# CY8C4125AZI-S433.net
KiCad netlist of a schematic drawn in Altium Designer
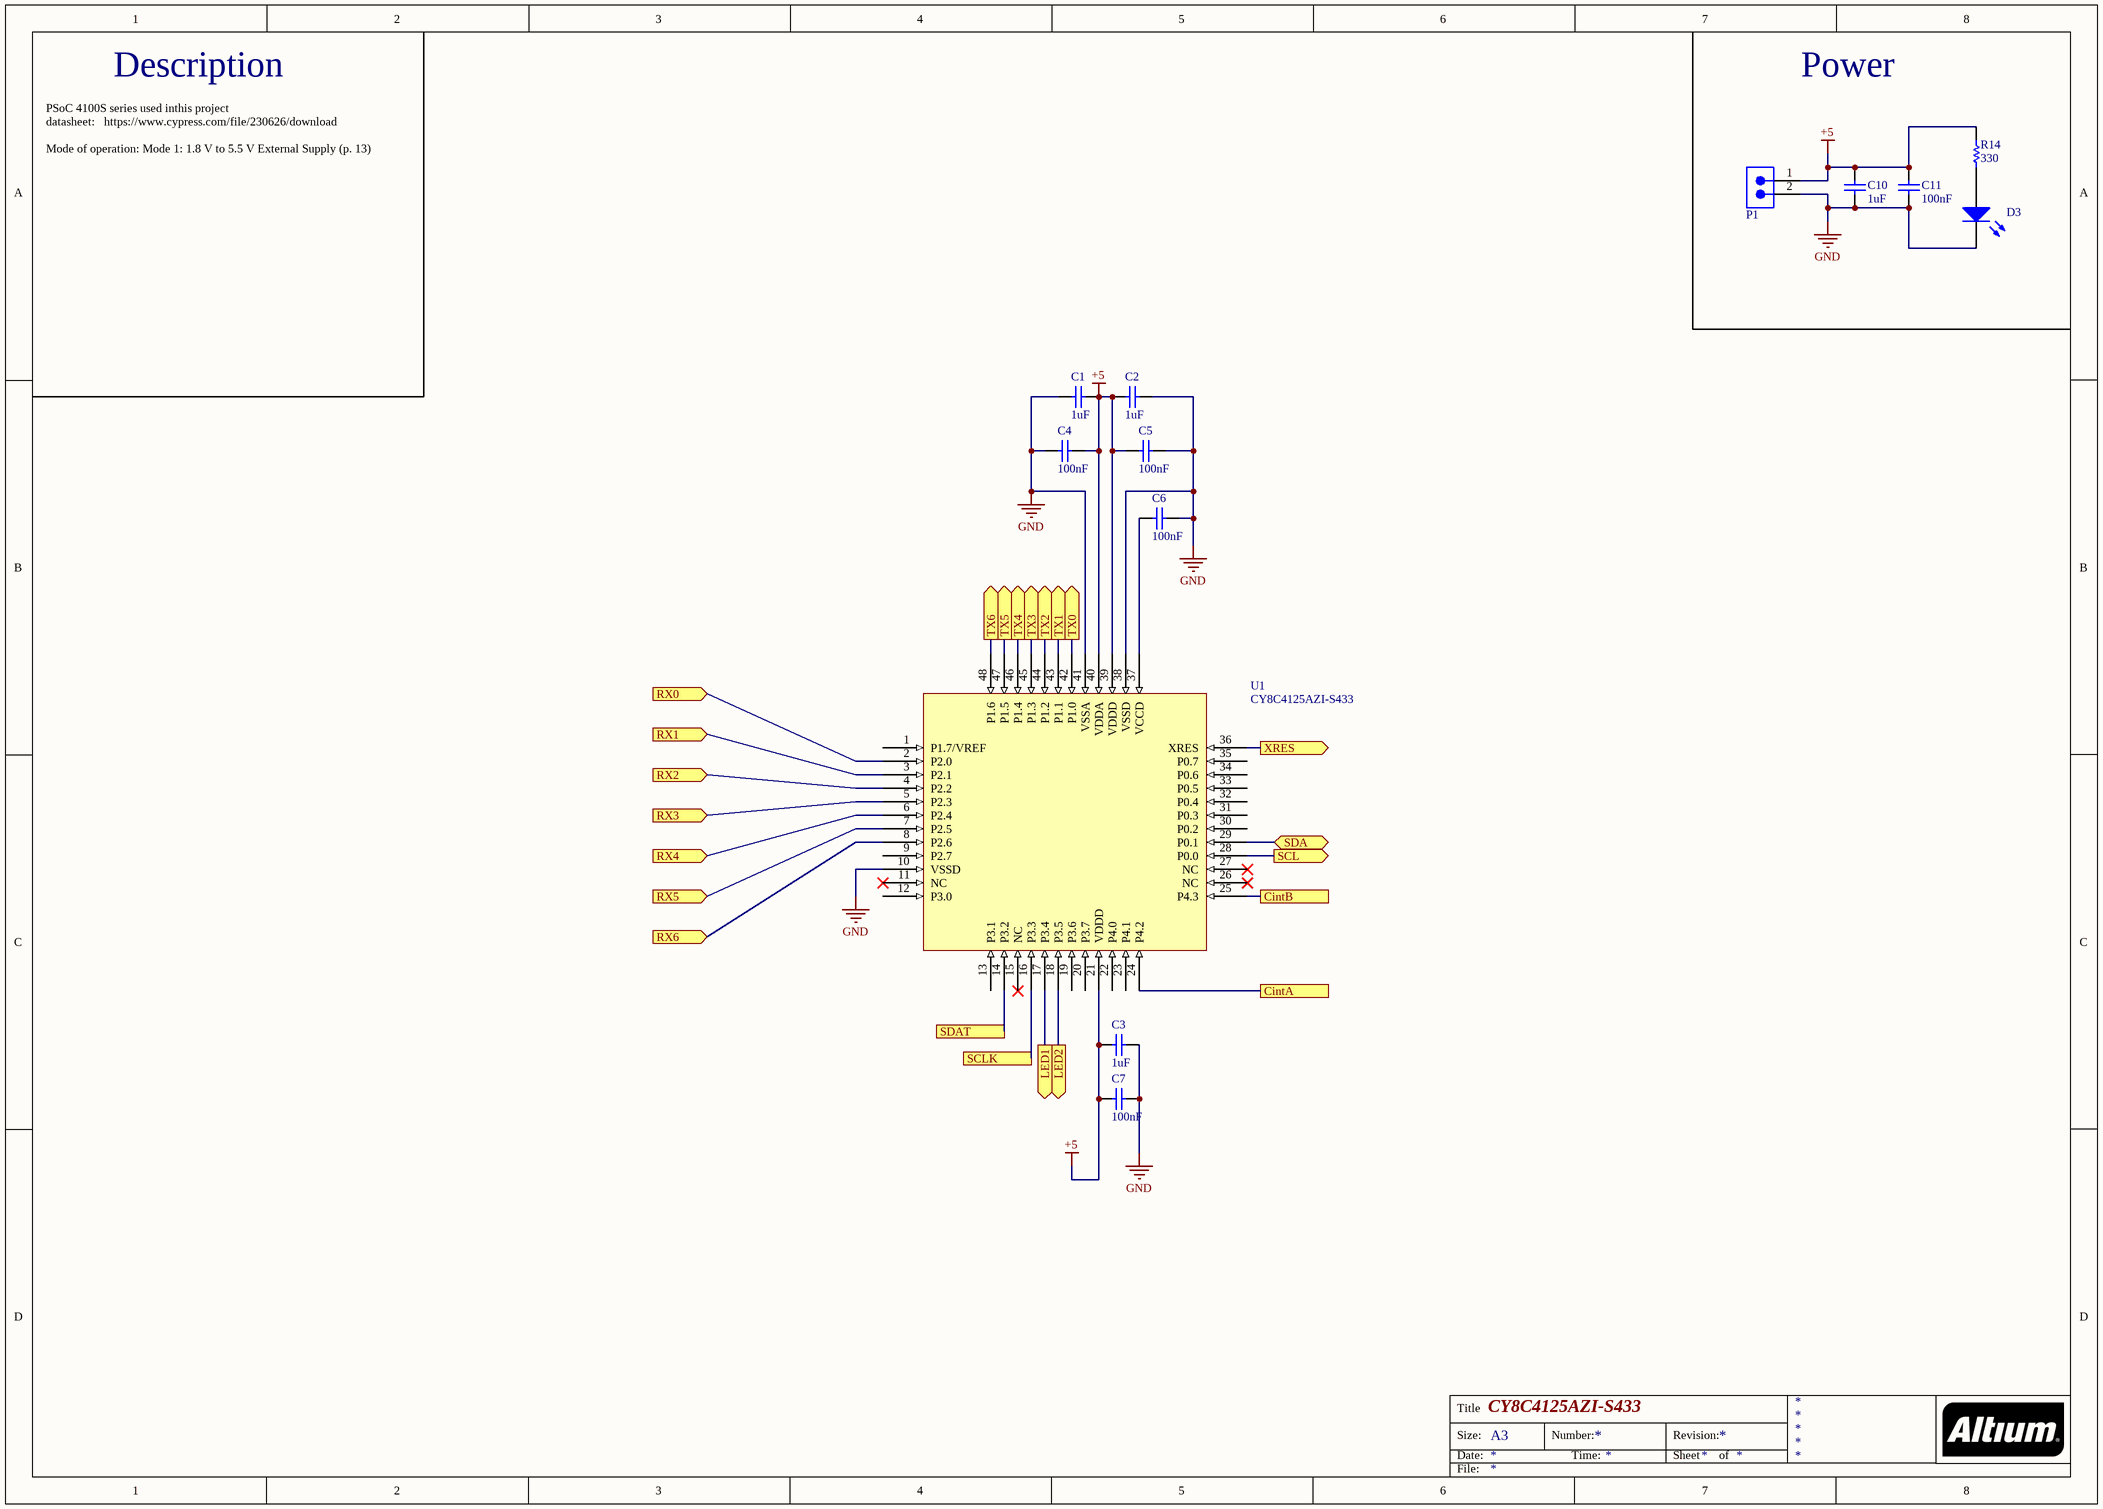
[diagram p0: CY8C4125AZI-S433.SchDoc]

(export (version "E")
  (design (tool "Eeschema 10.0.6"))
  (components
    (comp (ref "C1")
      (value "1uF")
      (footprint "CAPC0603(1608)100_N")
      (description "CAP 1uF 50V ±20% 0603 (1608 Metric) Thickness 1mm SMD")
      (fields (field (name "TOLERANCE") "Â±20%"))
      (libsource (lib "Altium Content Vault") (part "CAP"))
    )
    (comp (ref "C2")
      (value "1uF")
      (footprint "CAPC0603(1608)100_N")
      (description "CAP 1uF 50V ±20% 0603 (1608 Metric) Thickness 1mm SMD")
      (fields (field (name "TOLERANCE") "Â±20%"))
      (libsource (lib "Altium Content Vault") (part "CAP"))
    )
    (comp (ref "C3")
      (value "1uF")
      (footprint "CAPC0603(1608)100_N")
      (description "CAP 1uF 50V ±20% 0603 (1608 Metric) Thickness 1mm SMD")
      (fields (field (name "TOLERANCE") "Â±20%"))
      (libsource (lib "Altium Content Vault") (part "CAP"))
    )
    (comp (ref "C4")
      (value "100nF")
      (footprint "CAPC1608X90X20LL10")
      (fields
        (field (name "VOLTAGE") "50V")
        (field (name "TOLERANCE") "10%")
        (field (name "MANUFACTURER") "TDK")
      )
      (libsource (lib "Altium Content Vault") (part "CAP-NP-2"))
    )
    (comp (ref "C5")
      (value "100nF")
      (footprint "CAPC1608X90X20LL10")
      (fields
        (field (name "VOLTAGE") "50V")
        (field (name "TOLERANCE") "10%")
        (field (name "MANUFACTURER") "TDK")
      )
      (libsource (lib "Altium Content Vault") (part "CAP-NP-2"))
    )
    (comp (ref "C6")
      (value "100nF")
      (footprint "CAPC1608X90X20LL10")
      (fields
        (field (name "VOLTAGE") "50V")
        (field (name "TOLERANCE") "10%")
        (field (name "MANUFACTURER") "TDK")
      )
      (libsource (lib "Altium Content Vault") (part "CAP-NP-2"))
    )
    (comp (ref "C7")
      (value "100nF")
      (footprint "CAPC1608X90X20LL10")
      (fields
        (field (name "VOLTAGE") "50V")
        (field (name "TOLERANCE") "10%")
        (field (name "MANUFACTURER") "TDK")
      )
      (libsource (lib "Altium Content Vault") (part "CAP-NP-2"))
    )
    (comp (ref "C10")
      (value "1uF")
      (footprint "CAPC0603(1608)100_N")
      (description "CAP 1uF 50V ±20% 0603 (1608 Metric) Thickness 1mm SMD")
      (fields (field (name "TOLERANCE") "Â±20%"))
      (libsource (lib "Altium Content Vault") (part "CAP"))
    )
    (comp (ref "C11")
      (value "100nF")
      (footprint "CAPC1608X90X20LL10")
      (fields
        (field (name "VOLTAGE") "50V")
        (field (name "TOLERANCE") "10%")
        (field (name "MANUFACTURER") "TDK")
      )
      (libsource (lib "Altium Content Vault") (part "CAP-NP-2"))
    )
    (comp (ref "D3")
      (value "150060BS75000")
      (footprint "0603_A")
      (description "SMD mono-color Chip LED, WL-SMCW, Blue")
      (fields (field (name "MANUFACTURER") "Wuerth Elektronik"))
      (libsource (lib "Altium Content Vault") (part "WE-LED_K1A2-2"))
    )
    (comp (ref "P1")
      (value "MTLW-102-05-T-S-172")
      (footprint "SMTC-MTLW-102-05-X-S-172")
      (fields (field (name "MANUFACTURER") "Samtec"))
      (libsource (lib "Altium Content Vault") (part "SMTC-MTLW-102-05-X-S-172"))
    )
    (comp (ref "R14")
      (value "330")
      (footprint "RESC0603(1608)_L")
      (description "330R 0.1W 5% 0603 (1608 Metric)  SMD")
      (fields (field (name "TOLERANCE") "5 %") (field (name "POWER") "0.1 W"))
      (libsource (lib "Altium Content Vault") (part "RES"))
    )
    (comp (ref "U1")
      (value "CY8C4125AZI-S433")
      (footprint "CY8C4125AZI-S433")
      (libsource (lib "PSOC") (part "CY8C4125AZI-S433"))
    )
  )
  (nets
    (net (code "1") (name "+5") (class "Default")
      (node (ref "C1") (pin "2") (pinfunction "2_2") (pintype "passive"))
      (node (ref "C10") (pin "2") (pinfunction "2_2") (pintype "passive"))
      (node (ref "C11") (pin "2") (pinfunction "2_2") (pintype "passive"))
      (node (ref "C2") (pin "1") (pinfunction "1_1") (pintype "passive"))
      (node (ref "C3") (pin "1") (pinfunction "1_1") (pintype "passive"))
      (node (ref "C4") (pin "2") (pinfunction "2_2") (pintype "passive"))
      (node (ref "C5") (pin "1") (pinfunction "1_1") (pintype "passive"))
      (node (ref "C7") (pin "1") (pinfunction "1_1") (pintype "passive"))
      (node (ref "P1") (pin "1") (pinfunction "1_1") (pintype "passive"))
      (node (ref "R14") (pin "1") (pinfunction "1_1") (pintype "passive"))
      (node (ref "U1") (pin "21") (pinfunction "VDDD_21") (pintype "input"))
      (node (ref "U1") (pin "39") (pinfunction "VDDD_39") (pintype "input"))
      (node (ref "U1") (pin "40") (pinfunction "VDDA_40") (pintype "input"))
    )
    (net (code "2") (name "/CintA") (class "Default")
      (node (ref "U1") (pin "24") (pinfunction "P4.2_24") (pintype "input"))
    )
    (net (code "3") (name "/CintB") (class "Default")
      (node (ref "U1") (pin "25") (pinfunction "P4.3_25") (pintype "input"))
    )
    (net (code "4") (name "/LED1") (class "Default")
      (node (ref "U1") (pin "17") (pinfunction "P3.4_17") (pintype "input"))
    )
    (net (code "5") (name "/LED2") (class "Default")
      (node (ref "U1") (pin "18") (pinfunction "P3.5_18") (pintype "input"))
    )
    (net (code "6") (name "/RX0") (class "Default")
      (node (ref "U1") (pin "2") (pinfunction "P2.0_2") (pintype "input"))
    )
    (net (code "7") (name "/RX1") (class "Default")
      (node (ref "U1") (pin "3") (pinfunction "P2.1_3") (pintype "input"))
    )
    (net (code "8") (name "/RX2") (class "Default")
      (node (ref "U1") (pin "4") (pinfunction "P2.2_4") (pintype "input"))
    )
    (net (code "9") (name "/RX3") (class "Default")
      (node (ref "U1") (pin "5") (pinfunction "P2.3_5") (pintype "input"))
    )
    (net (code "10") (name "/RX4") (class "Default")
      (node (ref "U1") (pin "6") (pinfunction "P2.4_6") (pintype "input"))
    )
    (net (code "11") (name "/RX5") (class "Default")
      (node (ref "U1") (pin "7") (pinfunction "P2.5_7") (pintype "input"))
    )
    (net (code "12") (name "/RX6") (class "Default")
      (node (ref "U1") (pin "8") (pinfunction "P2.6_8") (pintype "input"))
    )
    (net (code "13") (name "/SCL") (class "Default")
      (node (ref "U1") (pin "28") (pinfunction "P0.0_28") (pintype "input"))
    )
    (net (code "14") (name "/SCLK") (class "Default")
      (node (ref "U1") (pin "16") (pinfunction "P3.3_16") (pintype "input"))
    )
    (net (code "15") (name "/SDA") (class "Default")
      (node (ref "U1") (pin "29") (pinfunction "P0.1_29") (pintype "input"))
    )
    (net (code "16") (name "/SDAT") (class "Default")
      (node (ref "U1") (pin "14") (pinfunction "P3.2_14") (pintype "input"))
    )
    (net (code "17") (name "/TX0") (class "Default")
      (node (ref "U1") (pin "42") (pinfunction "P1.0_42") (pintype "input"))
    )
    (net (code "18") (name "/TX1") (class "Default")
      (node (ref "U1") (pin "43") (pinfunction "P1.1_43") (pintype "input"))
    )
    (net (code "19") (name "/TX2") (class "Default")
      (node (ref "U1") (pin "44") (pinfunction "P1.2_44") (pintype "input"))
    )
    (net (code "20") (name "/TX3") (class "Default")
      (node (ref "U1") (pin "45") (pinfunction "P1.3_45") (pintype "input"))
    )
    (net (code "21") (name "/TX4") (class "Default")
      (node (ref "U1") (pin "46") (pinfunction "P1.4_46") (pintype "input"))
    )
    (net (code "22") (name "/TX5") (class "Default")
      (node (ref "U1") (pin "47") (pinfunction "P1.5_47") (pintype "input"))
    )
    (net (code "23") (name "/TX6") (class "Default")
      (node (ref "U1") (pin "48") (pinfunction "P1.6_48") (pintype "input"))
    )
    (net (code "24") (name "/XRES") (class "Default")
      (node (ref "U1") (pin "36") (pinfunction "XRES_36") (pintype "input"))
    )
    (net (code "25") (name "GND") (class "Default")
      (node (ref "C1") (pin "1") (pinfunction "1_1") (pintype "passive"))
      (node (ref "C10") (pin "1") (pinfunction "1_1") (pintype "passive"))
      (node (ref "C11") (pin "1") (pinfunction "1_1") (pintype "passive"))
      (node (ref "C2") (pin "2") (pinfunction "2_2") (pintype "passive"))
      (node (ref "C3") (pin "2") (pinfunction "2_2") (pintype "passive"))
      (node (ref "C4") (pin "1") (pinfunction "1_1") (pintype "passive"))
      (node (ref "C5") (pin "2") (pinfunction "2_2") (pintype "passive"))
      (node (ref "C6") (pin "2") (pinfunction "2_2") (pintype "passive"))
      (node (ref "C7") (pin "2") (pinfunction "2_2") (pintype "passive"))
      (node (ref "D3") (pin "1") (pinfunction "K_1") (pintype "passive"))
      (node (ref "P1") (pin "2") (pinfunction "2_2") (pintype "passive"))
      (node (ref "U1") (pin "10") (pinfunction "VSSD_10") (pintype "input"))
      (node (ref "U1") (pin "38") (pinfunction "VSSD_38") (pintype "input"))
      (node (ref "U1") (pin "41") (pinfunction "VSSA_41") (pintype "input"))
    )
    (net (code "26") (name "Net-(D3-A)") (class "Default")
      (node (ref "D3") (pin "2") (pinfunction "A_2") (pintype "passive"))
      (node (ref "R14") (pin "2") (pinfunction "2_2") (pintype "passive"))
    )
    (net (code "27") (name "Net-(U1-VCCD)") (class "Default")
      (node (ref "C6") (pin "1") (pinfunction "1_1") (pintype "passive"))
      (node (ref "U1") (pin "37") (pinfunction "VCCD_37") (pintype "input"))
    )
    (net (code "28") (name "unconnected-(U1-NC-Pad11)") (class "Default")
      (node (ref "U1") (pin "11") (pinfunction "NC_11") (pintype "input+no_connect"))
    )
    (net (code "29") (name "unconnected-(U1-NC-Pad15)") (class "Default")
      (node (ref "U1") (pin "15") (pinfunction "NC_15") (pintype "input+no_connect"))
    )
    (net (code "30") (name "unconnected-(U1-NC-Pad26)") (class "Default")
      (node (ref "U1") (pin "26") (pinfunction "NC_26") (pintype "input+no_connect"))
    )
    (net (code "31") (name "unconnected-(U1-NC-Pad27)") (class "Default")
      (node (ref "U1") (pin "27") (pinfunction "NC_27") (pintype "input+no_connect"))
    )
    (net (code "32") (name "unconnected-(U1-P0.2-Pad30)") (class "Default")
      (node (ref "U1") (pin "30") (pinfunction "P0.2_30") (pintype "input"))
    )
    (net (code "33") (name "unconnected-(U1-P0.3-Pad31)") (class "Default")
      (node (ref "U1") (pin "31") (pinfunction "P0.3_31") (pintype "input"))
    )
    (net (code "34") (name "unconnected-(U1-P0.4-Pad32)") (class "Default")
      (node (ref "U1") (pin "32") (pinfunction "P0.4_32") (pintype "input"))
    )
    (net (code "35") (name "unconnected-(U1-P0.5-Pad33)") (class "Default")
      (node (ref "U1") (pin "33") (pinfunction "P0.5_33") (pintype "input"))
    )
    (net (code "36") (name "unconnected-(U1-P0.6-Pad34)") (class "Default")
      (node (ref "U1") (pin "34") (pinfunction "P0.6_34") (pintype "input"))
    )
    (net (code "37") (name "unconnected-(U1-P0.7-Pad35)") (class "Default")
      (node (ref "U1") (pin "35") (pinfunction "P0.7_35") (pintype "input"))
    )
    (net (code "38") (name "unconnected-(U1-P1.7{slash}VREF-Pad1)") (class "Default")
      (node (ref "U1") (pin "1") (pinfunction "P1.7/VREF_1") (pintype "input"))
    )
    (net (code "39") (name "unconnected-(U1-P2.7-Pad9)") (class "Default")
      (node (ref "U1") (pin "9") (pinfunction "P2.7_9") (pintype "input"))
    )
    (net (code "40") (name "unconnected-(U1-P3.0-Pad12)") (class "Default")
      (node (ref "U1") (pin "12") (pinfunction "P3.0_12") (pintype "input"))
    )
    (net (code "41") (name "unconnected-(U1-P3.1-Pad13)") (class "Default")
      (node (ref "U1") (pin "13") (pinfunction "P3.1_13") (pintype "input"))
    )
    (net (code "42") (name "unconnected-(U1-P3.6-Pad19)") (class "Default")
      (node (ref "U1") (pin "19") (pinfunction "P3.6_19") (pintype "input"))
    )
    (net (code "43") (name "unconnected-(U1-P3.7-Pad20)") (class "Default")
      (node (ref "U1") (pin "20") (pinfunction "P3.7_20") (pintype "input"))
    )
    (net (code "44") (name "unconnected-(U1-P4.0-Pad22)") (class "Default")
      (node (ref "U1") (pin "22") (pinfunction "P4.0_22") (pintype "input"))
    )
    (net (code "45") (name "unconnected-(U1-P4.1-Pad23)") (class "Default")
      (node (ref "U1") (pin "23") (pinfunction "P4.1_23") (pintype "input"))
    )
  )
)
